# FDC9266_floppyboard.net
KiCad netlist of a schematic drawn in EAGLE
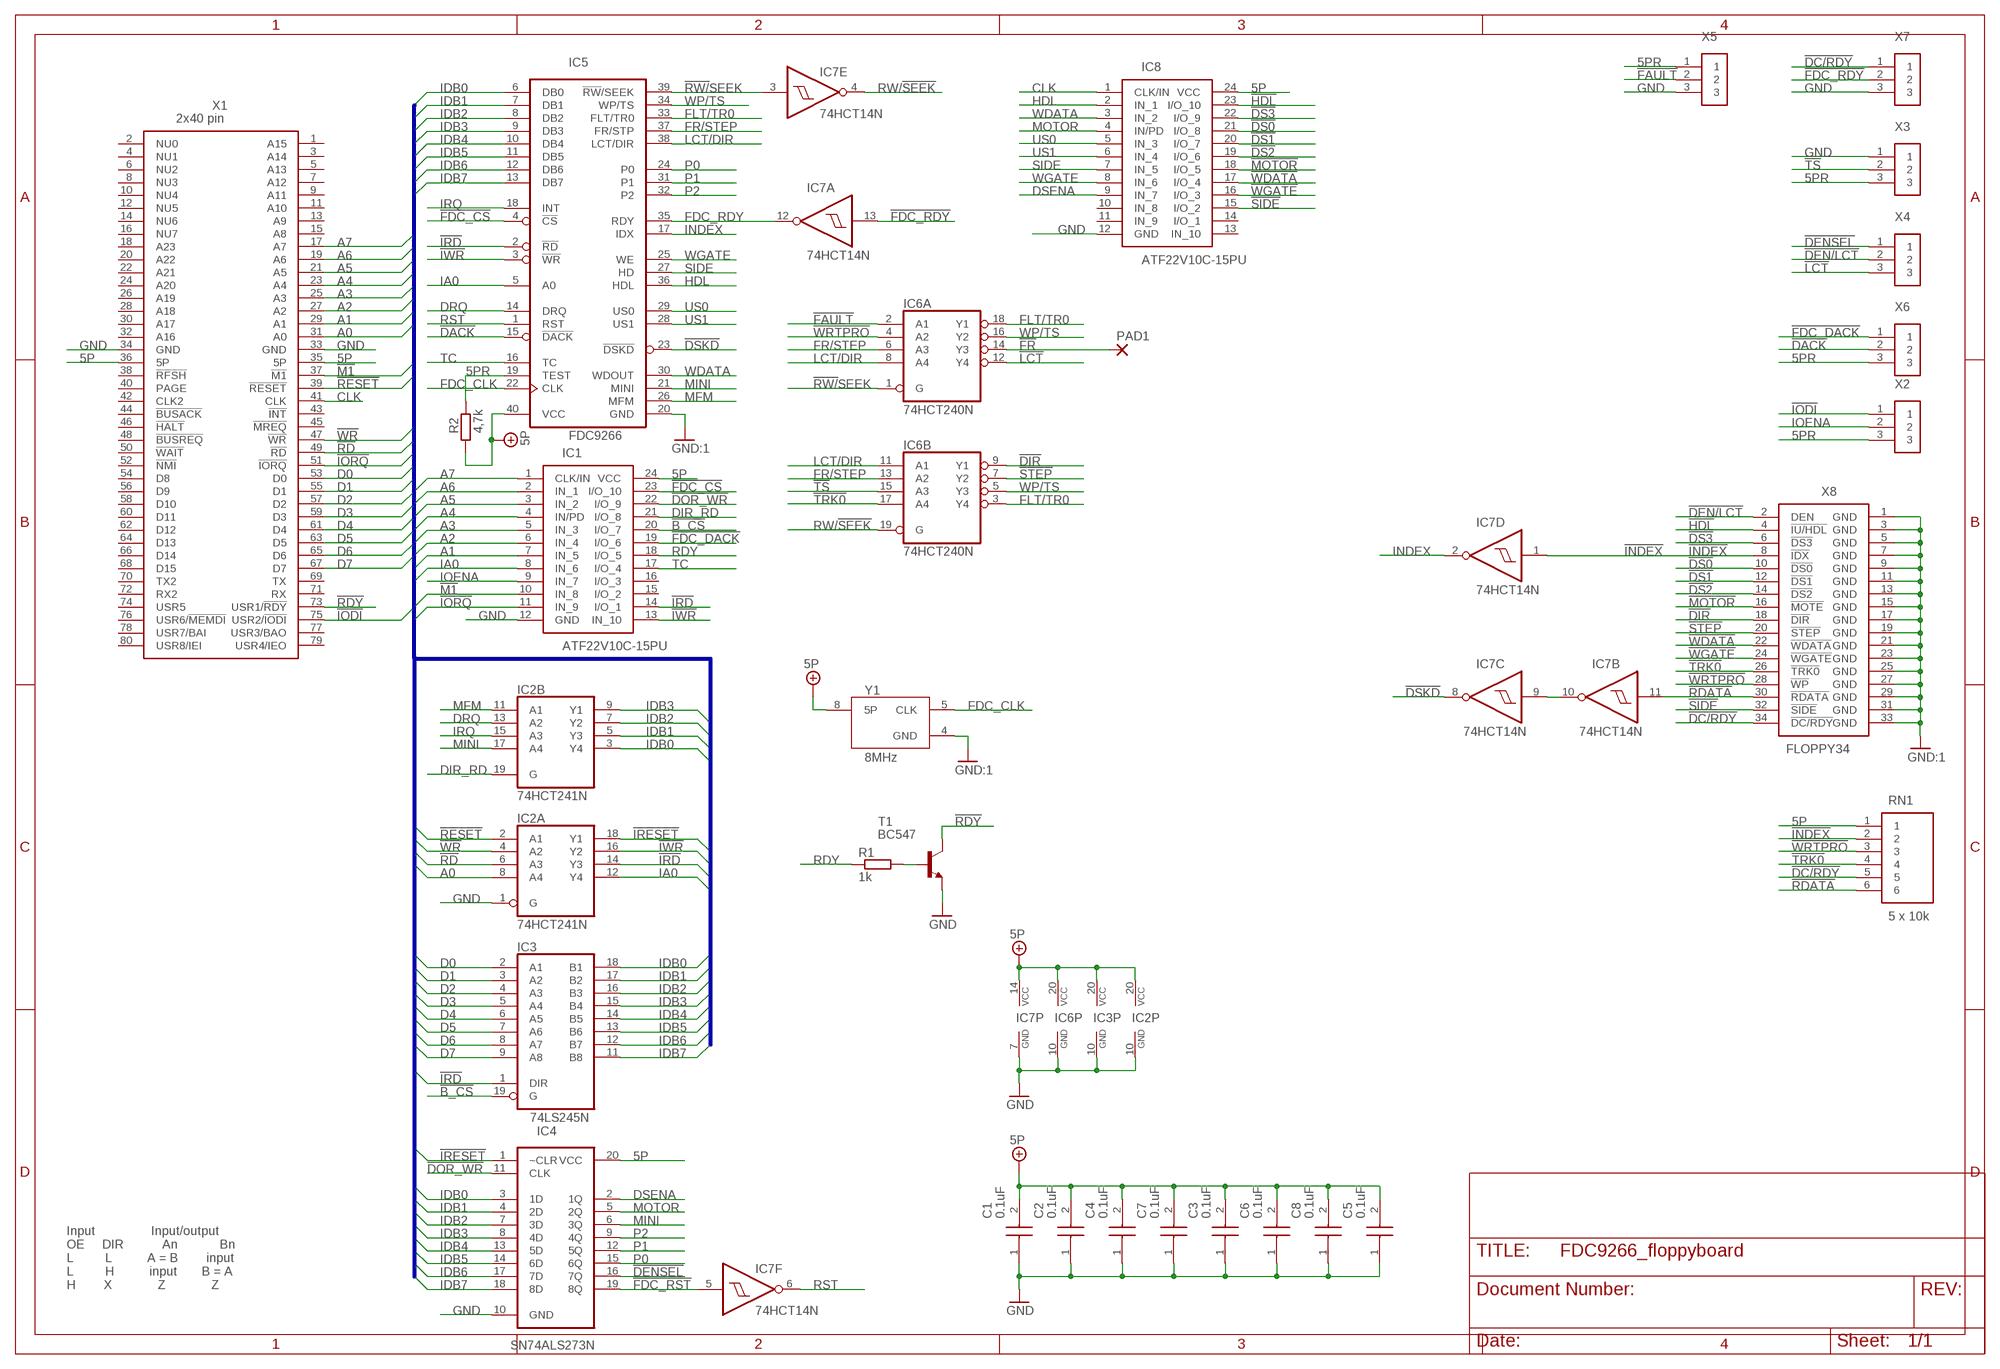
[diagram p0: schematic, sheet 1]

(export (version "E")
  (design (tool "Eeschema 10.0.6"))
  (components
    (comp (ref "C1")
      (value "0.1uF")
      (footprint "eagle-import:C315C103K5R5TA7303")
      (fields
        (field (name "ARROW_PART_NUMBER") "C315C103K5R5TA7303")
        (field (name "MOUSER_PART_NUMBER") "80-C315C103K5R-TR")
      )
      (libsource (lib "eagle-import") (part "C315C103K5R5TA7303"))
    )
    (comp (ref "C2")
      (value "0.1uF")
      (footprint "eagle-import:C315C103K5R5TA7303")
      (fields
        (field (name "ARROW_PART_NUMBER") "C315C103K5R5TA7303")
        (field (name "MOUSER_PART_NUMBER") "80-C315C103K5R-TR")
      )
      (libsource (lib "eagle-import") (part "C315C103K5R5TA7303"))
    )
    (comp (ref "C3")
      (value "0.1uF")
      (footprint "eagle-import:C315C103K5R5TA7303")
      (fields
        (field (name "ARROW_PART_NUMBER") "C315C103K5R5TA7303")
        (field (name "MOUSER_PART_NUMBER") "80-C315C103K5R-TR")
      )
      (libsource (lib "eagle-import") (part "C315C103K5R5TA7303"))
    )
    (comp (ref "C4")
      (value "0.1uF")
      (footprint "eagle-import:C315C103K5R5TA7303")
      (fields
        (field (name "ARROW_PART_NUMBER") "C315C103K5R5TA7303")
        (field (name "MOUSER_PART_NUMBER") "80-C315C103K5R-TR")
      )
      (libsource (lib "eagle-import") (part "C315C103K5R5TA7303"))
    )
    (comp (ref "C5")
      (value "0.1uF")
      (footprint "eagle-import:C315C103K5R5TA7303")
      (fields
        (field (name "ARROW_PART_NUMBER") "C315C103K5R5TA7303")
        (field (name "MOUSER_PART_NUMBER") "80-C315C103K5R-TR")
      )
      (libsource (lib "eagle-import") (part "C315C103K5R5TA7303"))
    )
    (comp (ref "C6")
      (value "0.1uF")
      (footprint "eagle-import:C315C103K5R5TA7303")
      (fields
        (field (name "ARROW_PART_NUMBER") "C315C103K5R5TA7303")
        (field (name "MOUSER_PART_NUMBER") "80-C315C103K5R-TR")
      )
      (libsource (lib "eagle-import") (part "C315C103K5R5TA7303"))
    )
    (comp (ref "C7")
      (value "0.1uF")
      (footprint "eagle-import:C315C103K5R5TA7303")
      (fields
        (field (name "ARROW_PART_NUMBER") "C315C103K5R5TA7303")
        (field (name "MOUSER_PART_NUMBER") "80-C315C103K5R-TR")
      )
      (libsource (lib "eagle-import") (part "C315C103K5R5TA7303"))
    )
    (comp (ref "C8")
      (value "0.1uF")
      (footprint "eagle-import:C315C103K5R5TA7303")
      (fields
        (field (name "ARROW_PART_NUMBER") "C315C103K5R5TA7303")
        (field (name "MOUSER_PART_NUMBER") "80-C315C103K5R-TR")
      )
      (libsource (lib "eagle-import") (part "C315C103K5R5TA7303"))
    )
    (comp (ref "IC1")
      (value "ATF22V10C-15PU")
      (footprint "eagle-import:DIP794W56P254L3188H533Q24N")
      (fields (field (name "MOUSER_PART_NUMBER") "556-AF22V10C15PU"))
      (libsource (lib "eagle-import") (part "ATF22V10C-15PU"))
    )
    (comp (ref "IC2")
      (value "74HCT241N")
      (footprint "eagle-import:DIL20")
      (libsource (lib "eagle-import") (part "74241NHCT"))
    )
    (comp (ref "IC3")
      (value "74LS245N")
      (footprint "eagle-import:DIL20")
      (libsource (lib "eagle-import") (part "74245NLS"))
    )
    (comp (ref "IC4")
      (value "SN74ALS273N")
      (footprint "eagle-import:DIP254P762X508-20")
      (libsource (lib "eagle-import") (part "SN74ALS273N"))
    )
    (comp (ref "IC5")
      (value "FDC9266")
      (footprint "eagle-import:DIP1550W53P254L5232H424Q40N")
      (libsource (lib "eagle-import") (part "FDC9266"))
    )
    (comp (ref "IC6")
      (value "74HCT240N")
      (footprint "eagle-import:DIL20")
      (libsource (lib "eagle-import") (part "74240NHCT"))
    )
    (comp (ref "IC7")
      (value "74HCT14N")
      (footprint "eagle-import:DIL14")
      (libsource (lib "eagle-import") (part "7414NHCT"))
    )
    (comp (ref "IC8")
      (value "ATF22V10C-15PU")
      (footprint "eagle-import:DIP794W56P254L3188H533Q24N")
      (fields (field (name "MOUSER_PART_NUMBER") "556-AF22V10C15PU"))
      (libsource (lib "eagle-import") (part "ATF22V10C-15PU"))
    )
    (comp (ref "PAD1")
      (value "WIREPAD1,6/0,8")
      (footprint "eagle-import:1,6_0,8")
      (libsource (lib "eagle-import") (part "WIREPAD1,6/0,8"))
    )
    (comp (ref "R1")
      (value "1k")
      (footprint "eagle-import:0207_10")
      (libsource (lib "eagle-import") (part "R_EU_020710"))
    )
    (comp (ref "R2")
      (value "4,7k")
      (footprint "eagle-import:0207_10")
      (libsource (lib "eagle-import") (part "R_EU_020710"))
    )
    (comp (ref "RN1")
      (value "5 x 10k")
      (footprint "eagle-import:4606X102103LF")
      (fields
        (field (name "ARROW_PART_NUMBER") "4606X-101-103LF")
        (field (name "MOUSER_PART_NUMBER") "652-4606X-1LF-10K")
      )
      (libsource (lib "eagle-import") (part "4606X-101-103LF"))
    )
    (comp (ref "T1")
      (value "BC547")
      (footprint "eagle-import:TO92")
      (libsource (lib "eagle-import") (part "BC547"))
    )
    (comp (ref "X1")
      (value "2x40 pin")
      (footprint "eagle-import:RC2014_80_RA")
      (libsource (lib "eagle-import") (part "RCBUS_80_RA"))
    )
    (comp (ref "X2")
      (value "TSW-103-07-G-S07")
      (footprint "eagle-import:TSW-103-XX-G-S")
      (fields (field (name "MF") "Samtec Inc.") (field (name "MPN") "TSW-103-07-G-S"))
      (libsource (lib "eagle-import") (part "TSW-103-07-G-S07"))
    )
    (comp (ref "X3")
      (value "TSW-103-07-G-S07")
      (footprint "eagle-import:TSW-103-XX-G-S")
      (fields (field (name "MF") "Samtec Inc.") (field (name "MPN") "TSW-103-07-G-S"))
      (libsource (lib "eagle-import") (part "TSW-103-07-G-S07"))
    )
    (comp (ref "X4")
      (value "TSW-103-07-G-S07")
      (footprint "eagle-import:TSW-103-XX-G-S")
      (fields (field (name "MF") "Samtec Inc.") (field (name "MPN") "TSW-103-07-G-S"))
      (libsource (lib "eagle-import") (part "TSW-103-07-G-S07"))
    )
    (comp (ref "X5")
      (value "TSW-103-07-G-S07")
      (footprint "eagle-import:TSW-103-XX-G-S")
      (fields (field (name "MF") "Samtec Inc.") (field (name "MPN") "TSW-103-07-G-S"))
      (libsource (lib "eagle-import") (part "TSW-103-07-G-S07"))
    )
    (comp (ref "X6")
      (value "TSW-103-07-G-S07")
      (footprint "eagle-import:TSW-103-XX-G-S")
      (fields (field (name "MF") "Samtec Inc.") (field (name "MPN") "TSW-103-07-G-S"))
      (libsource (lib "eagle-import") (part "TSW-103-07-G-S07"))
    )
    (comp (ref "X7")
      (value "TSW-103-07-G-S07")
      (footprint "eagle-import:TSW-103-XX-G-S")
      (fields (field (name "MF") "Samtec Inc.") (field (name "MPN") "TSW-103-07-G-S"))
      (libsource (lib "eagle-import") (part "TSW-103-07-G-S07"))
    )
    (comp (ref "X8")
      (value "FLOPPY34")
      (footprint "eagle-import:09185346323")
      (fields
        (field (name "ARROW_PART_NUMBER") "09185346323")
        (field (name "MOUSER_PART_NUMBER") "617-09-18-534-6323")
      )
      (libsource (lib "eagle-import") (part "FLOPPY34"))
    )
    (comp (ref "Y1")
      (value "8MHz")
      (footprint "eagle-import:ECS-2100AX-200")
      (fields
        (field (name "DIGIKEY_PART_NUMBER") "X964-ND")
        (field (name "MANUFACTURER") "ECS Inc.")
        (field (name "MPN") "ECS-2100AX-200")
        (field (name "CREATED_BY") "PCBLayout.com")
      )
      (libsource (lib "eagle-import") (part "ECS-2100AX-200"))
    )
  )
  (nets
    (net (code "1") (name "/5PR") (class "Default")
      (node (ref "IC5") (pin "19") (pinfunction "TEST_19") (pintype "input"))
      (node (ref "R2") (pin "2") (pinfunction "2_2") (pintype "passive"))
      (node (ref "X2") (pin "3") (pinfunction "3_3") (pintype "bidirectional"))
      (node (ref "X3") (pin "3") (pinfunction "3_3") (pintype "bidirectional"))
      (node (ref "X5") (pin "1") (pinfunction "1_1") (pintype "bidirectional"))
      (node (ref "X6") (pin "3") (pinfunction "3_3") (pintype "bidirectional"))
    )
    (net (code "2") (name "/A0") (class "Default")
      (node (ref "IC2") (pin "8") (pinfunction "A4_8") (pintype "input"))
      (node (ref "X1") (pin "31") (pinfunction "A0_31") (pintype "bidirectional"))
    )
    (net (code "3") (name "/A1") (class "Default")
      (node (ref "IC1") (pin "7") (pinfunction "IN_5_7") (pintype "bidirectional"))
      (node (ref "X1") (pin "29") (pinfunction "A1_29") (pintype "bidirectional"))
    )
    (net (code "4") (name "/A2") (class "Default")
      (node (ref "IC1") (pin "6") (pinfunction "IN_4_6") (pintype "bidirectional"))
      (node (ref "X1") (pin "27") (pinfunction "A2_27") (pintype "bidirectional"))
    )
    (net (code "5") (name "/A3") (class "Default")
      (node (ref "IC1") (pin "5") (pinfunction "IN_3_5") (pintype "bidirectional"))
      (node (ref "X1") (pin "25") (pinfunction "A3_25") (pintype "bidirectional"))
    )
    (net (code "6") (name "/A4") (class "Default")
      (node (ref "IC1") (pin "4") (pinfunction "IN/PD_4") (pintype "bidirectional"))
      (node (ref "X1") (pin "23") (pinfunction "A4_23") (pintype "bidirectional"))
    )
    (net (code "7") (name "/A5") (class "Default")
      (node (ref "IC1") (pin "3") (pinfunction "IN_2_3") (pintype "bidirectional"))
      (node (ref "X1") (pin "21") (pinfunction "A5_21") (pintype "bidirectional"))
    )
    (net (code "8") (name "/A6") (class "Default")
      (node (ref "IC1") (pin "2") (pinfunction "IN_1_2") (pintype "bidirectional"))
      (node (ref "X1") (pin "19") (pinfunction "A6_19") (pintype "bidirectional"))
    )
    (net (code "9") (name "/A7") (class "Default")
      (node (ref "IC1") (pin "1") (pinfunction "CLK/IN_1") (pintype "bidirectional"))
      (node (ref "X1") (pin "17") (pinfunction "A7_17") (pintype "bidirectional"))
    )
    (net (code "10") (name "/CLK") (class "Default")
      (node (ref "IC8") (pin "1") (pinfunction "CLK/IN_1") (pintype "bidirectional"))
      (node (ref "X1") (pin "41") (pinfunction "CLK_41") (pintype "bidirectional"))
    )
    (net (code "11") (name "/D0") (class "Default")
      (node (ref "IC3") (pin "2") (pinfunction "A1_2") (pintype "bidirectional"))
      (node (ref "X1") (pin "53") (pinfunction "D0_53") (pintype "bidirectional"))
    )
    (net (code "12") (name "/D1") (class "Default")
      (node (ref "IC3") (pin "3") (pinfunction "A2_3") (pintype "bidirectional"))
      (node (ref "X1") (pin "55") (pinfunction "D1_55") (pintype "bidirectional"))
    )
    (net (code "13") (name "/D2") (class "Default")
      (node (ref "IC3") (pin "4") (pinfunction "A3_4") (pintype "bidirectional"))
      (node (ref "X1") (pin "57") (pinfunction "D2_57") (pintype "bidirectional"))
    )
    (net (code "14") (name "/D3") (class "Default")
      (node (ref "IC3") (pin "5") (pinfunction "A4_5") (pintype "bidirectional"))
      (node (ref "X1") (pin "59") (pinfunction "D3_59") (pintype "bidirectional"))
    )
    (net (code "15") (name "/D4") (class "Default")
      (node (ref "IC3") (pin "6") (pinfunction "A5_6") (pintype "bidirectional"))
      (node (ref "X1") (pin "61") (pinfunction "D4_61") (pintype "bidirectional"))
    )
    (net (code "16") (name "/D5") (class "Default")
      (node (ref "IC3") (pin "7") (pinfunction "A6_7") (pintype "bidirectional"))
      (node (ref "X1") (pin "63") (pinfunction "D5_63") (pintype "bidirectional"))
    )
    (net (code "17") (name "/D6") (class "Default")
      (node (ref "IC3") (pin "8") (pinfunction "A7_8") (pintype "bidirectional"))
      (node (ref "X1") (pin "65") (pinfunction "D6_65") (pintype "bidirectional"))
    )
    (net (code "18") (name "/D7") (class "Default")
      (node (ref "IC3") (pin "9") (pinfunction "A8_9") (pintype "bidirectional"))
      (node (ref "X1") (pin "67") (pinfunction "D7_67") (pintype "bidirectional"))
    )
    (net (code "19") (name "/DIR_RD") (class "Default")
      (node (ref "IC1") (pin "21") (pinfunction "I/O_8_21") (pintype "bidirectional"))
      (node (ref "IC2") (pin "19") (pinfunction "G_19") (pintype "input"))
    )
    (net (code "20") (name "/DRQ") (class "Default")
      (node (ref "IC2") (pin "13") (pinfunction "A2_13") (pintype "input"))
      (node (ref "IC5") (pin "14") (pinfunction "DRQ_14") (pintype "output"))
    )
    (net (code "21") (name "/DSENA") (class "Default")
      (node (ref "IC4") (pin "2") (pinfunction "1Q_2") (pintype "output"))
      (node (ref "IC8") (pin "9") (pinfunction "IN_7_9") (pintype "bidirectional"))
    )
    (net (code "22") (name "/FDC_CLK") (class "Default")
      (node (ref "IC5") (pin "22") (pinfunction "CLK_22") (pintype "input"))
      (node (ref "Y1") (pin "5") (pinfunction "CLK_5") (pintype "output"))
    )
    (net (code "23") (name "/FDC_RDY") (class "Default")
      (node (ref "IC5") (pin "35") (pinfunction "RDY_35") (pintype "input"))
      (node (ref "IC7") (pin "12") (pinfunction "O_12") (pintype "output"))
    )
    (net (code "24") (name "/FLT{slash}TR0") (class "Default")
      (node (ref "IC5") (pin "33") (pinfunction "FLT/TR0_33") (pintype "input"))
      (node (ref "IC6") (pin "18") (pinfunction "Y1_18") (pintype "tri_state"))
      (node (ref "IC6") (pin "3") (pinfunction "Y4_3") (pintype "tri_state"))
    )
    (net (code "25") (name "/FR{slash}STEP") (class "Default")
      (node (ref "IC5") (pin "37") (pinfunction "FR/STP_37") (pintype "output"))
      (node (ref "IC6") (pin "13") (pinfunction "A2_13") (pintype "input"))
      (node (ref "IC6") (pin "6") (pinfunction "A3_6") (pintype "input"))
    )
    (net (code "26") (name "/HDL") (class "Default")
      (node (ref "IC5") (pin "36") (pinfunction "HDL_36") (pintype "output"))
      (node (ref "IC8") (pin "2") (pinfunction "IN_1_2") (pintype "bidirectional"))
    )
    (net (code "27") (name "/IA0") (class "Default")
      (node (ref "IC1") (pin "8") (pinfunction "IN_6_8") (pintype "bidirectional"))
      (node (ref "IC2") (pin "12") (pinfunction "Y4_12") (pintype "tri_state"))
      (node (ref "IC5") (pin "5") (pinfunction "A0_5") (pintype "input"))
    )
    (net (code "28") (name "/IDB0") (class "Default")
      (node (ref "IC2") (pin "3") (pinfunction "Y4_3") (pintype "tri_state"))
      (node (ref "IC3") (pin "18") (pinfunction "B1_18") (pintype "bidirectional"))
      (node (ref "IC4") (pin "3") (pinfunction "1D_3") (pintype "input"))
      (node (ref "IC5") (pin "6") (pinfunction "DB0_6") (pintype "bidirectional"))
    )
    (net (code "29") (name "/IDB1") (class "Default")
      (node (ref "IC2") (pin "5") (pinfunction "Y3_5") (pintype "tri_state"))
      (node (ref "IC3") (pin "17") (pinfunction "B2_17") (pintype "bidirectional"))
      (node (ref "IC4") (pin "4") (pinfunction "2D_4") (pintype "input"))
      (node (ref "IC5") (pin "7") (pinfunction "DB1_7") (pintype "bidirectional"))
    )
    (net (code "30") (name "/IDB2") (class "Default")
      (node (ref "IC2") (pin "7") (pinfunction "Y2_7") (pintype "tri_state"))
      (node (ref "IC3") (pin "16") (pinfunction "B3_16") (pintype "bidirectional"))
      (node (ref "IC4") (pin "7") (pinfunction "3D_7") (pintype "input"))
      (node (ref "IC5") (pin "8") (pinfunction "DB2_8") (pintype "bidirectional"))
    )
    (net (code "31") (name "/IDB3") (class "Default")
      (node (ref "IC2") (pin "9") (pinfunction "Y1_9") (pintype "tri_state"))
      (node (ref "IC3") (pin "15") (pinfunction "B4_15") (pintype "bidirectional"))
      (node (ref "IC4") (pin "8") (pinfunction "4D_8") (pintype "input"))
      (node (ref "IC5") (pin "9") (pinfunction "DB3_9") (pintype "bidirectional"))
    )
    (net (code "32") (name "/IDB4") (class "Default")
      (node (ref "IC3") (pin "14") (pinfunction "B5_14") (pintype "bidirectional"))
      (node (ref "IC4") (pin "13") (pinfunction "5D_13") (pintype "input"))
      (node (ref "IC5") (pin "10") (pinfunction "DB4_10") (pintype "bidirectional"))
    )
    (net (code "33") (name "/IDB5") (class "Default")
      (node (ref "IC3") (pin "13") (pinfunction "B6_13") (pintype "bidirectional"))
      (node (ref "IC4") (pin "14") (pinfunction "6D_14") (pintype "input"))
      (node (ref "IC5") (pin "11") (pinfunction "DB5_11") (pintype "bidirectional"))
    )
    (net (code "34") (name "/IDB6") (class "Default")
      (node (ref "IC3") (pin "12") (pinfunction "B7_12") (pintype "bidirectional"))
      (node (ref "IC4") (pin "17") (pinfunction "7D_17") (pintype "input"))
      (node (ref "IC5") (pin "12") (pinfunction "DB6_12") (pintype "bidirectional"))
    )
    (net (code "35") (name "/IDB7") (class "Default")
      (node (ref "IC3") (pin "11") (pinfunction "B8_11") (pintype "bidirectional"))
      (node (ref "IC4") (pin "18") (pinfunction "8D_18") (pintype "input"))
      (node (ref "IC5") (pin "13") (pinfunction "DB7_13") (pintype "bidirectional"))
    )
    (net (code "36") (name "/INDEX") (class "Default")
      (node (ref "IC5") (pin "17") (pinfunction "IDX_17") (pintype "input"))
      (node (ref "IC7") (pin "2") (pinfunction "O_2") (pintype "output"))
    )
    (net (code "37") (name "/IOENA") (class "Default")
      (node (ref "IC1") (pin "9") (pinfunction "IN_7_9") (pintype "bidirectional"))
      (node (ref "X2") (pin "2") (pinfunction "2_2") (pintype "bidirectional"))
    )
    (net (code "38") (name "/IRQ") (class "Default")
      (node (ref "IC2") (pin "15") (pinfunction "A3_15") (pintype "input"))
      (node (ref "IC5") (pin "18") (pinfunction "INT_18") (pintype "output"))
    )
    (net (code "39") (name "/LCT{slash}DIR") (class "Default")
      (node (ref "IC5") (pin "38") (pinfunction "LCT/DIR_38") (pintype "output"))
      (node (ref "IC6") (pin "11") (pinfunction "A1_11") (pintype "input"))
      (node (ref "IC6") (pin "8") (pinfunction "A4_8") (pintype "input"))
    )
    (net (code "40") (name "/MFM") (class "Default")
      (node (ref "IC2") (pin "11") (pinfunction "A1_11") (pintype "input"))
      (node (ref "IC5") (pin "26") (pinfunction "MFM_26") (pintype "output"))
    )
    (net (code "41") (name "/MINI") (class "Default")
      (node (ref "IC2") (pin "17") (pinfunction "A4_17") (pintype "input"))
      (node (ref "IC4") (pin "6") (pinfunction "3Q_6") (pintype "output"))
      (node (ref "IC5") (pin "21") (pinfunction "MINI_21") (pintype "input"))
    )
    (net (code "42") (name "/MOTOR") (class "Default")
      (node (ref "IC4") (pin "5") (pinfunction "2Q_5") (pintype "output"))
      (node (ref "IC8") (pin "4") (pinfunction "IN/PD_4") (pintype "bidirectional"))
    )
    (net (code "43") (name "/P0") (class "Default")
      (node (ref "IC4") (pin "15") (pinfunction "6Q_15") (pintype "output"))
      (node (ref "IC5") (pin "24") (pinfunction "P0_24") (pintype "input"))
    )
    (net (code "44") (name "/P1") (class "Default")
      (node (ref "IC4") (pin "12") (pinfunction "5Q_12") (pintype "output"))
      (node (ref "IC5") (pin "31") (pinfunction "P1_31") (pintype "input"))
    )
    (net (code "45") (name "/P2") (class "Default")
      (node (ref "IC4") (pin "9") (pinfunction "4Q_9") (pintype "output"))
      (node (ref "IC5") (pin "32") (pinfunction "P2_32") (pintype "input"))
    )
    (net (code "46") (name "/RDY") (class "Default")
      (node (ref "IC1") (pin "18") (pinfunction "I/O_5_18") (pintype "bidirectional"))
      (node (ref "R1") (pin "1") (pinfunction "1_1") (pintype "passive"))
    )
    (net (code "47") (name "/RST") (class "Default")
      (node (ref "IC5") (pin "1") (pinfunction "RST_1") (pintype "input"))
      (node (ref "IC7") (pin "6") (pinfunction "O_6") (pintype "output"))
    )
    (net (code "48") (name "/RW{slash}~{SEEK}") (class "Default")
      (node (ref "IC6") (pin "19") (pinfunction "G_19") (pintype "input"))
      (node (ref "IC7") (pin "4") (pinfunction "O_4") (pintype "output"))
    )
    (net (code "49") (name "/SIDE") (class "Default")
      (node (ref "IC5") (pin "27") (pinfunction "HD_27") (pintype "output"))
      (node (ref "IC8") (pin "7") (pinfunction "IN_5_7") (pintype "bidirectional"))
    )
    (net (code "50") (name "/TC") (class "Default")
      (node (ref "IC1") (pin "17") (pinfunction "I/O_4_17") (pintype "bidirectional"))
      (node (ref "IC5") (pin "16") (pinfunction "TC_16") (pintype "input"))
    )
    (net (code "51") (name "/US0") (class "Default")
      (node (ref "IC5") (pin "29") (pinfunction "US0_29") (pintype "output"))
      (node (ref "IC8") (pin "5") (pinfunction "IN_3_5") (pintype "bidirectional"))
    )
    (net (code "52") (name "/US1") (class "Default")
      (node (ref "IC5") (pin "28") (pinfunction "US1_28") (pintype "output"))
      (node (ref "IC8") (pin "6") (pinfunction "IN_4_6") (pintype "bidirectional"))
    )
    (net (code "53") (name "/WDATA") (class "Default")
      (node (ref "IC5") (pin "30") (pinfunction "WDOUT_30") (pintype "output"))
      (node (ref "IC8") (pin "3") (pinfunction "IN_2_3") (pintype "bidirectional"))
    )
    (net (code "54") (name "/WGATE") (class "Default")
      (node (ref "IC5") (pin "25") (pinfunction "WE_25") (pintype "output"))
      (node (ref "IC8") (pin "8") (pinfunction "IN_6_8") (pintype "bidirectional"))
    )
    (net (code "55") (name "/WP{slash}TS") (class "Default")
      (node (ref "IC5") (pin "34") (pinfunction "WP/TS_34") (pintype "input"))
      (node (ref "IC6") (pin "16") (pinfunction "Y2_16") (pintype "tri_state"))
      (node (ref "IC6") (pin "5") (pinfunction "Y3_5") (pintype "tri_state"))
    )
    (net (code "56") (name "/~{B_CS}") (class "Default")
      (node (ref "IC1") (pin "20") (pinfunction "I/O_7_20") (pintype "bidirectional"))
      (node (ref "IC3") (pin "19") (pinfunction "G_19") (pintype "input"))
    )
    (net (code "57") (name "/~{DACK}") (class "Default")
      (node (ref "IC5") (pin "15") (pinfunction "~{DACK}_15") (pintype "input"))
      (node (ref "X6") (pin "2") (pinfunction "2_2") (pintype "bidirectional"))
    )
    (net (code "58") (name "/~{DC{slash}RDY}") (class "Default")
      (node (ref "RN1") (pin "5") (pinfunction "5_5") (pintype "bidirectional"))
      (node (ref "X7") (pin "1") (pinfunction "1_1") (pintype "bidirectional"))
      (node (ref "X8") (pin "34") (pinfunction "~{DC/RDY}_34") (pintype "output"))
    )
    (net (code "59") (name "/~{DENSEL}") (class "Default")
      (node (ref "IC4") (pin "16") (pinfunction "7Q_16") (pintype "output"))
      (node (ref "X4") (pin "1") (pinfunction "1_1") (pintype "bidirectional"))
    )
    (net (code "60") (name "/~{DEN{slash}LCT}") (class "Default")
      (node (ref "X4") (pin "2") (pinfunction "2_2") (pintype "bidirectional"))
      (node (ref "X8") (pin "2") (pinfunction "DEN_2") (pintype "input"))
    )
    (net (code "61") (name "/~{DIR}") (class "Default")
      (node (ref "IC6") (pin "9") (pinfunction "Y1_9") (pintype "tri_state"))
      (node (ref "X8") (pin "18") (pinfunction "~{DIR}_18") (pintype "input"))
    )
    (net (code "62") (name "/~{DOR_WR}") (class "Default")
      (node (ref "IC1") (pin "22") (pinfunction "I/O_9_22") (pintype "bidirectional"))
      (node (ref "IC4") (pin "11") (pinfunction "CLK_11") (pintype "input"))
    )
    (net (code "63") (name "/~{DS0}") (class "Default")
      (node (ref "IC8") (pin "21") (pinfunction "I/O_8_21") (pintype "bidirectional"))
      (node (ref "X8") (pin "10") (pinfunction "~{DS0}_10") (pintype "input"))
    )
    (net (code "64") (name "/~{DS1}") (class "Default")
      (node (ref "IC8") (pin "20") (pinfunction "I/O_7_20") (pintype "bidirectional"))
      (node (ref "X8") (pin "12") (pinfunction "~{DS1}_12") (pintype "input"))
    )
    (net (code "65") (name "/~{DS2}") (class "Default")
      (node (ref "IC8") (pin "19") (pinfunction "I/O_6_19") (pintype "bidirectional"))
      (node (ref "X8") (pin "14") (pinfunction "~{DS2}_14") (pintype "input"))
    )
    (net (code "66") (name "/~{DS3}") (class "Default")
      (node (ref "IC8") (pin "22") (pinfunction "I/O_9_22") (pintype "bidirectional"))
      (node (ref "X8") (pin "6") (pinfunction "~{DS3}_6") (pintype "input"))
    )
    (net (code "67") (name "/~{DSKD}") (class "Default")
      (node (ref "IC5") (pin "23") (pinfunction "~{DSKD}_23") (pintype "input"))
      (node (ref "IC7") (pin "8") (pinfunction "O_8") (pintype "output"))
    )
    (net (code "68") (name "/~{FAULT}") (class "Default")
      (node (ref "IC6") (pin "2") (pinfunction "A1_2") (pintype "input"))
      (node (ref "X5") (pin "2") (pinfunction "2_2") (pintype "bidirectional"))
    )
    (net (code "69") (name "/~{FDC_CS}") (class "Default")
      (node (ref "IC1") (pin "23") (pinfunction "I/O_10_23") (pintype "bidirectional"))
      (node (ref "IC5") (pin "4") (pinfunction "~{CS}_4") (pintype "input"))
    )
    (net (code "70") (name "/~{FDC_DACK}") (class "Default")
      (node (ref "IC1") (pin "19") (pinfunction "I/O_6_19") (pintype "bidirectional"))
      (node (ref "X6") (pin "1") (pinfunction "1_1") (pintype "bidirectional"))
    )
    (net (code "71") (name "/~{FDC_RDY}") (class "Default")
      (node (ref "IC7") (pin "13") (pinfunction "I_13") (pintype "input"))
      (node (ref "X7") (pin "2") (pinfunction "2_2") (pintype "bidirectional"))
    )
    (net (code "72") (name "/~{FDC_RST}") (class "Default")
      (node (ref "IC4") (pin "19") (pinfunction "8Q_19") (pintype "output"))
      (node (ref "IC7") (pin "5") (pinfunction "I_5") (pintype "input"))
    )
    (net (code "73") (name "/~{FR}") (class "Default")
      (node (ref "IC6") (pin "14") (pinfunction "Y3_14") (pintype "tri_state"))
      (node (ref "PAD1") (pin "1") (pinfunction "P_1") (pintype "passive"))
    )
    (net (code "74") (name "/~{HDL}") (class "Default")
      (node (ref "IC8") (pin "23") (pinfunction "I/O_10_23") (pintype "bidirectional"))
      (node (ref "X8") (pin "4") (pinfunction "~{IU/HDL}_4") (pintype "input"))
    )
    (net (code "75") (name "/~{INDEX}") (class "Default")
      (node (ref "IC7") (pin "1") (pinfunction "I_1") (pintype "input"))
      (node (ref "RN1") (pin "2") (pinfunction "2_2") (pintype "bidirectional"))
      (node (ref "X8") (pin "8") (pinfunction "~{IDX}_8") (pintype "output"))
    )
    (net (code "76") (name "/~{IODI}") (class "Default")
      (node (ref "X1") (pin "75") (pinfunction "USR2/~{IODI}_75") (pintype "bidirectional"))
      (node (ref "X2") (pin "1") (pinfunction "1_1") (pintype "bidirectional"))
    )
    (net (code "77") (name "/~{IORQ}") (class "Default")
      (node (ref "IC1") (pin "11") (pinfunction "IN_9_11") (pintype "bidirectional"))
      (node (ref "X1") (pin "51") (pinfunction "~{IORQ}_51") (pintype "bidirectional"))
    )
    (net (code "78") (name "/~{IRD}") (class "Default")
      (node (ref "IC1") (pin "14") (pinfunction "I/O_1_14") (pintype "bidirectional"))
      (node (ref "IC2") (pin "14") (pinfunction "Y3_14") (pintype "tri_state"))
      (node (ref "IC3") (pin "1") (pinfunction "DIR_1") (pintype "input"))
      (node (ref "IC5") (pin "2") (pinfunction "~{RD}_2") (pintype "input"))
    )
    (net (code "79") (name "/~{IRESET}") (class "Default")
      (node (ref "IC2") (pin "18") (pinfunction "Y1_18") (pintype "tri_state"))
      (node (ref "IC4") (pin "1") (pinfunction "~{CLR}_1") (pintype "input"))
    )
    (net (code "80") (name "/~{IWR}") (class "Default")
      (node (ref "IC1") (pin "13") (pinfunction "IN_10_13") (pintype "bidirectional"))
      (node (ref "IC2") (pin "16") (pinfunction "Y2_16") (pintype "tri_state"))
      (node (ref "IC5") (pin "3") (pinfunction "~{WR}_3") (pintype "input"))
    )
    (net (code "81") (name "/~{LCT}") (class "Default")
      (node (ref "IC6") (pin "12") (pinfunction "Y4_12") (pintype "tri_state"))
      (node (ref "X4") (pin "3") (pinfunction "3_3") (pintype "bidirectional"))
    )
    (net (code "82") (name "/~{M1}") (class "Default")
      (node (ref "IC1") (pin "10") (pinfunction "IN_8_10") (pintype "bidirectional"))
      (node (ref "X1") (pin "37") (pinfunction "~{M1}_37") (pintype "bidirectional"))
    )
    (net (code "83") (name "/~{MOTOR}") (class "Default")
      (node (ref "IC8") (pin "18") (pinfunction "I/O_5_18") (pintype "bidirectional"))
      (node (ref "X8") (pin "16") (pinfunction "~{MOTE}_16") (pintype "input"))
    )
    (net (code "84") (name "/~{RDATA}") (class "Default")
      (node (ref "IC7") (pin "11") (pinfunction "I_11") (pintype "input"))
      (node (ref "RN1") (pin "6") (pinfunction "6_6") (pintype "bidirectional"))
      (node (ref "X8") (pin "30") (pinfunction "~{RDATA}_30") (pintype "output"))
    )
    (net (code "85") (name "/~{RDY}") (class "Default")
      (node (ref "T1") (pin "3") (pinfunction "C_3") (pintype "passive"))
      (node (ref "X1") (pin "73") (pinfunction "USR1/~{RDY}_73") (pintype "bidirectional"))
    )
    (net (code "86") (name "/~{RD}") (class "Default")
      (node (ref "IC2") (pin "6") (pinfunction "A3_6") (pintype "input"))
      (node (ref "X1") (pin "49") (pinfunction "~{RD}_49") (pintype "bidirectional"))
    )
    (net (code "87") (name "/~{RESET}") (class "Default")
      (node (ref "IC2") (pin "2") (pinfunction "A1_2") (pintype "input"))
      (node (ref "X1") (pin "39") (pinfunction "~{RESET}_39") (pintype "bidirectional"))
    )
    (net (code "88") (name "/~{RW{slash}}SEEK") (class "Default")
      (node (ref "IC5") (pin "39") (pinfunction "~{RW}/SEEK_39") (pintype "output"))
      (node (ref "IC6") (pin "1") (pinfunction "G_1") (pintype "input"))
      (node (ref "IC7") (pin "3") (pinfunction "I_3") (pintype "input"))
    )
    (net (code "89") (name "/~{SIDE}") (class "Default")
      (node (ref "IC8") (pin "15") (pinfunction "I/O_2_15") (pintype "bidirectional"))
      (node (ref "X8") (pin "32") (pinfunction "~{SIDE}_32") (pintype "input"))
    )
    (net (code "90") (name "/~{STEP}") (class "Default")
      (node (ref "IC6") (pin "7") (pinfunction "Y2_7") (pintype "tri_state"))
      (node (ref "X8") (pin "20") (pinfunction "~{STEP}_20") (pintype "input"))
    )
    (net (code "91") (name "/~{TRK0}") (class "Default")
      (node (ref "IC6") (pin "17") (pinfunction "A4_17") (pintype "input"))
      (node (ref "RN1") (pin "4") (pinfunction "4_4") (pintype "bidirectional"))
      (node (ref "X8") (pin "26") (pinfunction "~{TRK0}_26") (pintype "output"))
    )
    (net (code "92") (name "/~{TS}") (class "Default")
      (node (ref "IC6") (pin "15") (pinfunction "A3_15") (pintype "input"))
      (node (ref "X3") (pin "2") (pinfunction "2_2") (pintype "bidirectional"))
    )
    (net (code "93") (name "/~{WDATA}") (class "Default")
      (node (ref "IC8") (pin "17") (pinfunction "I/O_4_17") (pintype "bidirectional"))
      (node (ref "X8") (pin "22") (pinfunction "~{WDATA}_22") (pintype "input"))
    )
    (net (code "94") (name "/~{WGATE}") (class "Default")
      (node (ref "IC8") (pin "16") (pinfunction "I/O_3_16") (pintype "bidirectional"))
      (node (ref "X8") (pin "24") (pinfunction "~{WGATE}_24") (pintype "input"))
    )
    (net (code "95") (name "/~{WRTPRO}") (class "Default")
      (node (ref "IC6") (pin "4") (pinfunction "A2_4") (pintype "input"))
      (node (ref "RN1") (pin "3") (pinfunction "3_3") (pintype "bidirectional"))
      (node (ref "X8") (pin "28") (pinfunction "~{WP}_28") (pintype "output"))
    )
    (net (code "96") (name "/~{WR}") (class "Default")
      (node (ref "IC2") (pin "4") (pinfunction "A2_4") (pintype "input"))
      (node (ref "X1") (pin "47") (pinfunction "~{WR}_47") (pintype "bidirectional"))
    )
    (net (code "97") (name "5P") (class "Default")
      (node (ref "C1") (pin "2") (pinfunction "2_2") (pintype "bidirectional"))
      (node (ref "C2") (pin "2") (pinfunction "2_2") (pintype "bidirectional"))
      (node (ref "C3") (pin "2") (pinfunction "2_2") (pintype "bidirectional"))
      (node (ref "C4") (pin "2") (pinfunction "2_2") (pintype "bidirectional"))
      (node (ref "C5") (pin "2") (pinfunction "2_2") (pintype "bidirectional"))
      (node (ref "C6") (pin "2") (pinfunction "2_2") (pintype "bidirectional"))
      (node (ref "C7") (pin "2") (pinfunction "2_2") (pintype "bidirectional"))
      (node (ref "C8") (pin "2") (pinfunction "2_2") (pintype "bidirectional"))
      (node (ref "IC1") (pin "24") (pinfunction "VCC_24") (pintype "bidirectional"))
      (node (ref "IC2") (pin "20") (pinfunction "VCC_20") (pintype "power_in"))
      (node (ref "IC3") (pin "20") (pinfunction "VCC_20") (pintype "power_in"))
      (node (ref "IC4") (pin "20") (pinfunction "VCC_20") (pintype "power_in"))
      (node (ref "IC5") (pin "40") (pinfunction "VCC_40") (pintype "power_in"))
      (node (ref "IC6") (pin "20") (pinfunction "VCC_20") (pintype "power_in"))
      (node (ref "IC7") (pin "14") (pinfunction "VCC_14") (pintype "power_in"))
      (node (ref "IC8") (pin "24") (pinfunction "VCC_24") (pintype "bidirectional"))
      (node (ref "R2") (pin "1") (pinfunction "1_1") (pintype "passive"))
      (node (ref "RN1") (pin "1") (pinfunction "1_1") (pintype "bidirectional"))
      (node (ref "X1") (pin "35") (pinfunction "5P_35") (pintype "power_in"))
      (node (ref "X1") (pin "36") (pinfunction "5P_36") (pintype "power_in"))
      (node (ref "Y1") (pin "8") (pinfunction "5P_8") (pintype "power_in"))
    )
    (net (code "98") (name "GND") (class "Default")
      (node (ref "C1") (pin "1") (pinfunction "1_1") (pintype "bidirectional"))
      (node (ref "C2") (pin "1") (pinfunction "1_1") (pintype "bidirectional"))
      (node (ref "C3") (pin "1") (pinfunction "1_1") (pintype "bidirectional"))
      (node (ref "C4") (pin "1") (pinfunction "1_1") (pintype "bidirectional"))
      (node (ref "C5") (pin "1") (pinfunction "1_1") (pintype "bidirectional"))
      (node (ref "C6") (pin "1") (pinfunction "1_1") (pintype "bidirectional"))
      (node (ref "C7") (pin "1") (pinfunction "1_1") (pintype "bidirectional"))
      (node (ref "C8") (pin "1") (pinfunction "1_1") (pintype "bidirectional"))
      (node (ref "IC1") (pin "12") (pinfunction "GND_12") (pintype "bidirectional"))
      (node (ref "IC2") (pin "1") (pinfunction "G_1") (pintype "input"))
      (node (ref "IC2") (pin "10") (pinfunction "GND_10") (pintype "power_in"))
      (node (ref "IC3") (pin "10") (pinfunction "GND_10") (pintype "power_in"))
      (node (ref "IC4") (pin "10") (pinfunction "GND_10") (pintype "power_in"))
      (node (ref "IC5") (pin "20") (pinfunction "GND_20") (pintype "power_in"))
      (node (ref "IC6") (pin "10") (pinfunction "GND_10") (pintype "power_in"))
      (node (ref "IC7") (pin "7") (pinfunction "GND_7") (pintype "power_in"))
      (node (ref "IC8") (pin "12") (pinfunction "GND_12") (pintype "bidirectional"))
      (node (ref "T1") (pin "1") (pinfunction "E_1") (pintype "passive"))
      (node (ref "X1") (pin "33") (pinfunction "GND_33") (pintype "power_in"))
      (node (ref "X1") (pin "34") (pinfunction "GND_34") (pintype "power_in"))
      (node (ref "X3") (pin "1") (pinfunction "1_1") (pintype "bidirectional"))
      (node (ref "X5") (pin "3") (pinfunction "3_3") (pintype "bidirectional"))
      (node (ref "X7") (pin "3") (pinfunction "3_3") (pintype "bidirectional"))
      (node (ref "X8") (pin "1") (pinfunction "GND_1") (pintype "power_in"))
      (node (ref "X8") (pin "11") (pinfunction "GND_11") (pintype "power_in"))
      (node (ref "X8") (pin "13") (pinfunction "GND_13") (pintype "power_in"))
      (node (ref "X8") (pin "15") (pinfunction "GND_15") (pintype "power_in"))
      (node (ref "X8") (pin "17") (pinfunction "GND_17") (pintype "power_in"))
      (node (ref "X8") (pin "19") (pinfunction "GND_19") (pintype "power_in"))
      (node (ref "X8") (pin "21") (pinfunction "GND_21") (pintype "power_in"))
      (node (ref "X8") (pin "23") (pinfunction "GND_23") (pintype "power_in"))
      (node (ref "X8") (pin "25") (pinfunction "GND_25") (pintype "power_in"))
      (node (ref "X8") (pin "27") (pinfunction "GND_27") (pintype "power_in"))
      (node (ref "X8") (pin "29") (pinfunction "GND_29") (pintype "power_in"))
      (node (ref "X8") (pin "3") (pinfunction "GND_3") (pintype "power_in"))
      (node (ref "X8") (pin "31") (pinfunction "GND_31") (pintype "power_in"))
      (node (ref "X8") (pin "33") (pinfunction "GND_33") (pintype "power_in"))
      (node (ref "X8") (pin "5") (pinfunction "GND_5") (pintype "power_in"))
      (node (ref "X8") (pin "7") (pinfunction "GND_7") (pintype "power_in"))
      (node (ref "X8") (pin "9") (pinfunction "GND_9") (pintype "power_in"))
      (node (ref "Y1") (pin "4") (pinfunction "GND_4") (pintype "power_in"))
    )
    (net (code "99") (name "Net-(IC7B-O)") (class "Default")
      (node (ref "IC7") (pin "10") (pinfunction "O_10") (pintype "output"))
      (node (ref "IC7") (pin "9") (pinfunction "I_9") (pintype "input"))
    )
    (net (code "100") (name "Net-(T1-B)") (class "Default")
      (node (ref "R1") (pin "2") (pinfunction "2_2") (pintype "passive"))
      (node (ref "T1") (pin "2") (pinfunction "B_2") (pintype "passive"))
    )
    (net (code "101") (name "unconnected-(IC1-I{slash}O_2-Pad15)") (class "Default")
      (node (ref "IC1") (pin "15") (pinfunction "I/O_2_15") (pintype "bidirectional"))
    )
    (net (code "102") (name "unconnected-(IC1-I{slash}O_3-Pad16)") (class "Default")
      (node (ref "IC1") (pin "16") (pinfunction "I/O_3_16") (pintype "bidirectional"))
    )
    (net (code "103") (name "unconnected-(IC8-IN_8-Pad10)") (class "Default")
      (node (ref "IC8") (pin "10") (pinfunction "IN_8_10") (pintype "bidirectional"))
    )
    (net (code "104") (name "unconnected-(IC8-IN_9-Pad11)") (class "Default")
      (node (ref "IC8") (pin "11") (pinfunction "IN_9_11") (pintype "bidirectional"))
    )
    (net (code "105") (name "unconnected-(IC8-IN_10-Pad13)") (class "Default")
      (node (ref "IC8") (pin "13") (pinfunction "IN_10_13") (pintype "bidirectional"))
    )
    (net (code "106") (name "unconnected-(IC8-I{slash}O_1-Pad14)") (class "Default")
      (node (ref "IC8") (pin "14") (pinfunction "I/O_1_14") (pintype "bidirectional"))
    )
    (net (code "107") (name "unconnected-(X1-A8-Pad15)") (class "Default")
      (node (ref "X1") (pin "15") (pinfunction "A8_15") (pintype "bidirectional"))
    )
    (net (code "108") (name "unconnected-(X1-A9-Pad13)") (class "Default")
      (node (ref "X1") (pin "13") (pinfunction "A9_13") (pintype "bidirectional"))
    )
    (net (code "109") (name "unconnected-(X1-A10-Pad11)") (class "Default")
      (node (ref "X1") (pin "11") (pinfunction "A10_11") (pintype "bidirectional"))
    )
    (net (code "110") (name "unconnected-(X1-A11-Pad9)") (class "Default")
      (node (ref "X1") (pin "9") (pinfunction "A11_9") (pintype "bidirectional"))
    )
    (net (code "111") (name "unconnected-(X1-A12-Pad7)") (class "Default")
      (node (ref "X1") (pin "7") (pinfunction "A12_7") (pintype "bidirectional"))
    )
    (net (code "112") (name "unconnected-(X1-A13-Pad5)") (class "Default")
      (node (ref "X1") (pin "5") (pinfunction "A13_5") (pintype "bidirectional"))
    )
    (net (code "113") (name "unconnected-(X1-A14-Pad3)") (class "Default")
      (node (ref "X1") (pin "3") (pinfunction "A14_3") (pintype "bidirectional"))
    )
    (net (code "114") (name "unconnected-(X1-A15-Pad1)") (class "Default")
      (node (ref "X1") (pin "1") (pinfunction "A15_1") (pintype "bidirectional"))
    )
    (net (code "115") (name "unconnected-(X1-A16-Pad32)") (class "Default")
      (node (ref "X1") (pin "32") (pinfunction "A16_32") (pintype "bidirectional"))
    )
    (net (code "116") (name "unconnected-(X1-A17-Pad30)") (class "Default")
      (node (ref "X1") (pin "30") (pinfunction "A17_30") (pintype "bidirectional"))
    )
    (net (code "117") (name "unconnected-(X1-A18-Pad28)") (class "Default")
      (node (ref "X1") (pin "28") (pinfunction "A18_28") (pintype "bidirectional"))
    )
    (net (code "118") (name "unconnected-(X1-A19-Pad26)") (class "Default")
      (node (ref "X1") (pin "26") (pinfunction "A19_26") (pintype "bidirectional"))
    )
    (net (code "119") (name "unconnected-(X1-A20-Pad24)") (class "Default")
      (node (ref "X1") (pin "24") (pinfunction "A20_24") (pintype "bidirectional"))
    )
    (net (code "120") (name "unconnected-(X1-A21-Pad22)") (class "Default")
      (node (ref "X1") (pin "22") (pinfunction "A21_22") (pintype "bidirectional"))
    )
    (net (code "121") (name "unconnected-(X1-A22-Pad20)") (class "Default")
      (node (ref "X1") (pin "20") (pinfunction "A22_20") (pintype "bidirectional"))
    )
    (net (code "122") (name "unconnected-(X1-A23-Pad18)") (class "Default")
      (node (ref "X1") (pin "18") (pinfunction "A23_18") (pintype "bidirectional"))
    )
    (net (code "123") (name "unconnected-(X1-CLK2-Pad42)") (class "Default")
      (node (ref "X1") (pin "42") (pinfunction "CLK2_42") (pintype "bidirectional"))
    )
    (net (code "124") (name "unconnected-(X1-D8-Pad54)") (class "Default")
      (node (ref "X1") (pin "54") (pinfunction "D8_54") (pintype "bidirectional"))
    )
    (net (code "125") (name "unconnected-(X1-D9-Pad56)") (class "Default")
      (node (ref "X1") (pin "56") (pinfunction "D9_56") (pintype "bidirectional"))
    )
    (net (code "126") (name "unconnected-(X1-D10-Pad58)") (class "Default")
      (node (ref "X1") (pin "58") (pinfunction "D10_58") (pintype "bidirectional"))
    )
    (net (code "127") (name "unconnected-(X1-D11-Pad60)") (class "Default")
      (node (ref "X1") (pin "60") (pinfunction "D11_60") (pintype "bidirectional"))
    )
    (net (code "128") (name "unconnected-(X1-D12-Pad62)") (class "Default")
      (node (ref "X1") (pin "62") (pinfunction "D12_62") (pintype "bidirectional"))
    )
    (net (code "129") (name "unconnected-(X1-D13-Pad64)") (class "Default")
      (node (ref "X1") (pin "64") (pinfunction "D13_64") (pintype "bidirectional"))
    )
    (net (code "130") (name "unconnected-(X1-D14-Pad66)") (class "Default")
      (node (ref "X1") (pin "66") (pinfunction "D14_66") (pintype "bidirectional"))
    )
    (net (code "131") (name "unconnected-(X1-D15-Pad68)") (class "Default")
      (node (ref "X1") (pin "68") (pinfunction "D15_68") (pintype "bidirectional"))
    )
    (net (code "132") (name "unconnected-(X1-NU0-Pad2)") (class "Default")
      (node (ref "X1") (pin "2") (pinfunction "NU0_2") (pintype "bidirectional"))
    )
    (net (code "133") (name "unconnected-(X1-NU1-Pad4)") (class "Default")
      (node (ref "X1") (pin "4") (pinfunction "NU1_4") (pintype "bidirectional"))
    )
    (net (code "134") (name "unconnected-(X1-NU2-Pad6)") (class "Default")
      (node (ref "X1") (pin "6") (pinfunction "NU2_6") (pintype "bidirectional"))
    )
    (net (code "135") (name "unconnected-(X1-NU3-Pad8)") (class "Default")
      (node (ref "X1") (pin "8") (pinfunction "NU3_8") (pintype "bidirectional"))
    )
    (net (code "136") (name "unconnected-(X1-NU4-Pad10)") (class "Default")
      (node (ref "X1") (pin "10") (pinfunction "NU4_10") (pintype "bidirectional"))
    )
    (net (code "137") (name "unconnected-(X1-NU5-Pad12)") (class "Default")
      (node (ref "X1") (pin "12") (pinfunction "NU5_12") (pintype "bidirectional"))
    )
    (net (code "138") (name "unconnected-(X1-NU6-Pad14)") (class "Default")
      (node (ref "X1") (pin "14") (pinfunction "NU6_14") (pintype "bidirectional"))
    )
    (net (code "139") (name "unconnected-(X1-NU7-Pad16)") (class "Default")
      (node (ref "X1") (pin "16") (pinfunction "NU7_16") (pintype "bidirectional"))
    )
    (net (code "140") (name "unconnected-(X1-PAGE-Pad40)") (class "Default")
      (node (ref "X1") (pin "40") (pinfunction "PAGE_40") (pintype "bidirectional"))
    )
    (net (code "141") (name "unconnected-(X1-RX-Pad71)") (class "Default")
      (node (ref "X1") (pin "71") (pinfunction "RX_71") (pintype "bidirectional"))
    )
    (net (code "142") (name "unconnected-(X1-RX2-Pad72)") (class "Default")
      (node (ref "X1") (pin "72") (pinfunction "RX2_72") (pintype "bidirectional"))
    )
    (net (code "143") (name "unconnected-(X1-TX-Pad69)") (class "Default")
      (node (ref "X1") (pin "69") (pinfunction "TX_69") (pintype "bidirectional"))
    )
    (net (code "144") (name "unconnected-(X1-TX2-Pad70)") (class "Default")
      (node (ref "X1") (pin "70") (pinfunction "TX2_70") (pintype "bidirectional"))
    )
    (net (code "145") (name "unconnected-(X1-USR3{slash}BAO-Pad77)") (class "Default")
      (node (ref "X1") (pin "77") (pinfunction "USR3/BAO_77") (pintype "bidirectional"))
    )
    (net (code "146") (name "unconnected-(X1-USR4{slash}IEO-Pad79)") (class "Default")
      (node (ref "X1") (pin "79") (pinfunction "USR4/IEO_79") (pintype "bidirectional"))
    )
    (net (code "147") (name "unconnected-(X1-USR5-Pad74)") (class "Default")
      (node (ref "X1") (pin "74") (pinfunction "USR5_74") (pintype "bidirectional"))
    )
    (net (code "148") (name "unconnected-(X1-USR6{slash}~{MEMDI}-Pad76)") (class "Default")
      (node (ref "X1") (pin "76") (pinfunction "USR6/~{MEMDI}_76") (pintype "bidirectional"))
    )
    (net (code "149") (name "unconnected-(X1-USR7{slash}BAI-Pad78)") (class "Default")
      (node (ref "X1") (pin "78") (pinfunction "USR7/BAI_78") (pintype "bidirectional"))
    )
    (net (code "150") (name "unconnected-(X1-USR8{slash}IEI-Pad80)") (class "Default")
      (node (ref "X1") (pin "80") (pinfunction "USR8/IEI_80") (pintype "bidirectional"))
    )
    (net (code "151") (name "unconnected-(X1-~{BUSACK}-Pad44)") (class "Default")
      (node (ref "X1") (pin "44") (pinfunction "~{BUSACK}_44") (pintype "bidirectional"))
    )
    (net (code "152") (name "unconnected-(X1-~{BUSREQ}-Pad48)") (class "Default")
      (node (ref "X1") (pin "48") (pinfunction "~{BUSREQ}_48") (pintype "bidirectional"))
    )
    (net (code "153") (name "unconnected-(X1-~{HALT}-Pad46)") (class "Default")
      (node (ref "X1") (pin "46") (pinfunction "~{HALT}_46") (pintype "bidirectional"))
    )
    (net (code "154") (name "unconnected-(X1-~{INT}-Pad43)") (class "Default")
      (node (ref "X1") (pin "43") (pinfunction "~{INT}_43") (pintype "bidirectional"))
    )
    (net (code "155") (name "unconnected-(X1-~{MREQ}-Pad45)") (class "Default")
      (node (ref "X1") (pin "45") (pinfunction "~{MREQ}_45") (pintype "bidirectional"))
    )
    (net (code "156") (name "unconnected-(X1-~{NMI}-Pad52)") (class "Default")
      (node (ref "X1") (pin "52") (pinfunction "~{NMI}_52") (pintype "bidirectional"))
    )
    (net (code "157") (name "unconnected-(X1-~{RFSH}-Pad38)") (class "Default")
      (node (ref "X1") (pin "38") (pinfunction "~{RFSH}_38") (pintype "bidirectional"))
    )
    (net (code "158") (name "unconnected-(X1-~{WAIT}-Pad50)") (class "Default")
      (node (ref "X1") (pin "50") (pinfunction "~{WAIT}_50") (pintype "bidirectional"))
    )
  )
)
